# 2xVCA_SMD.net
KiCad netlist of a schematic drawn in EAGLE
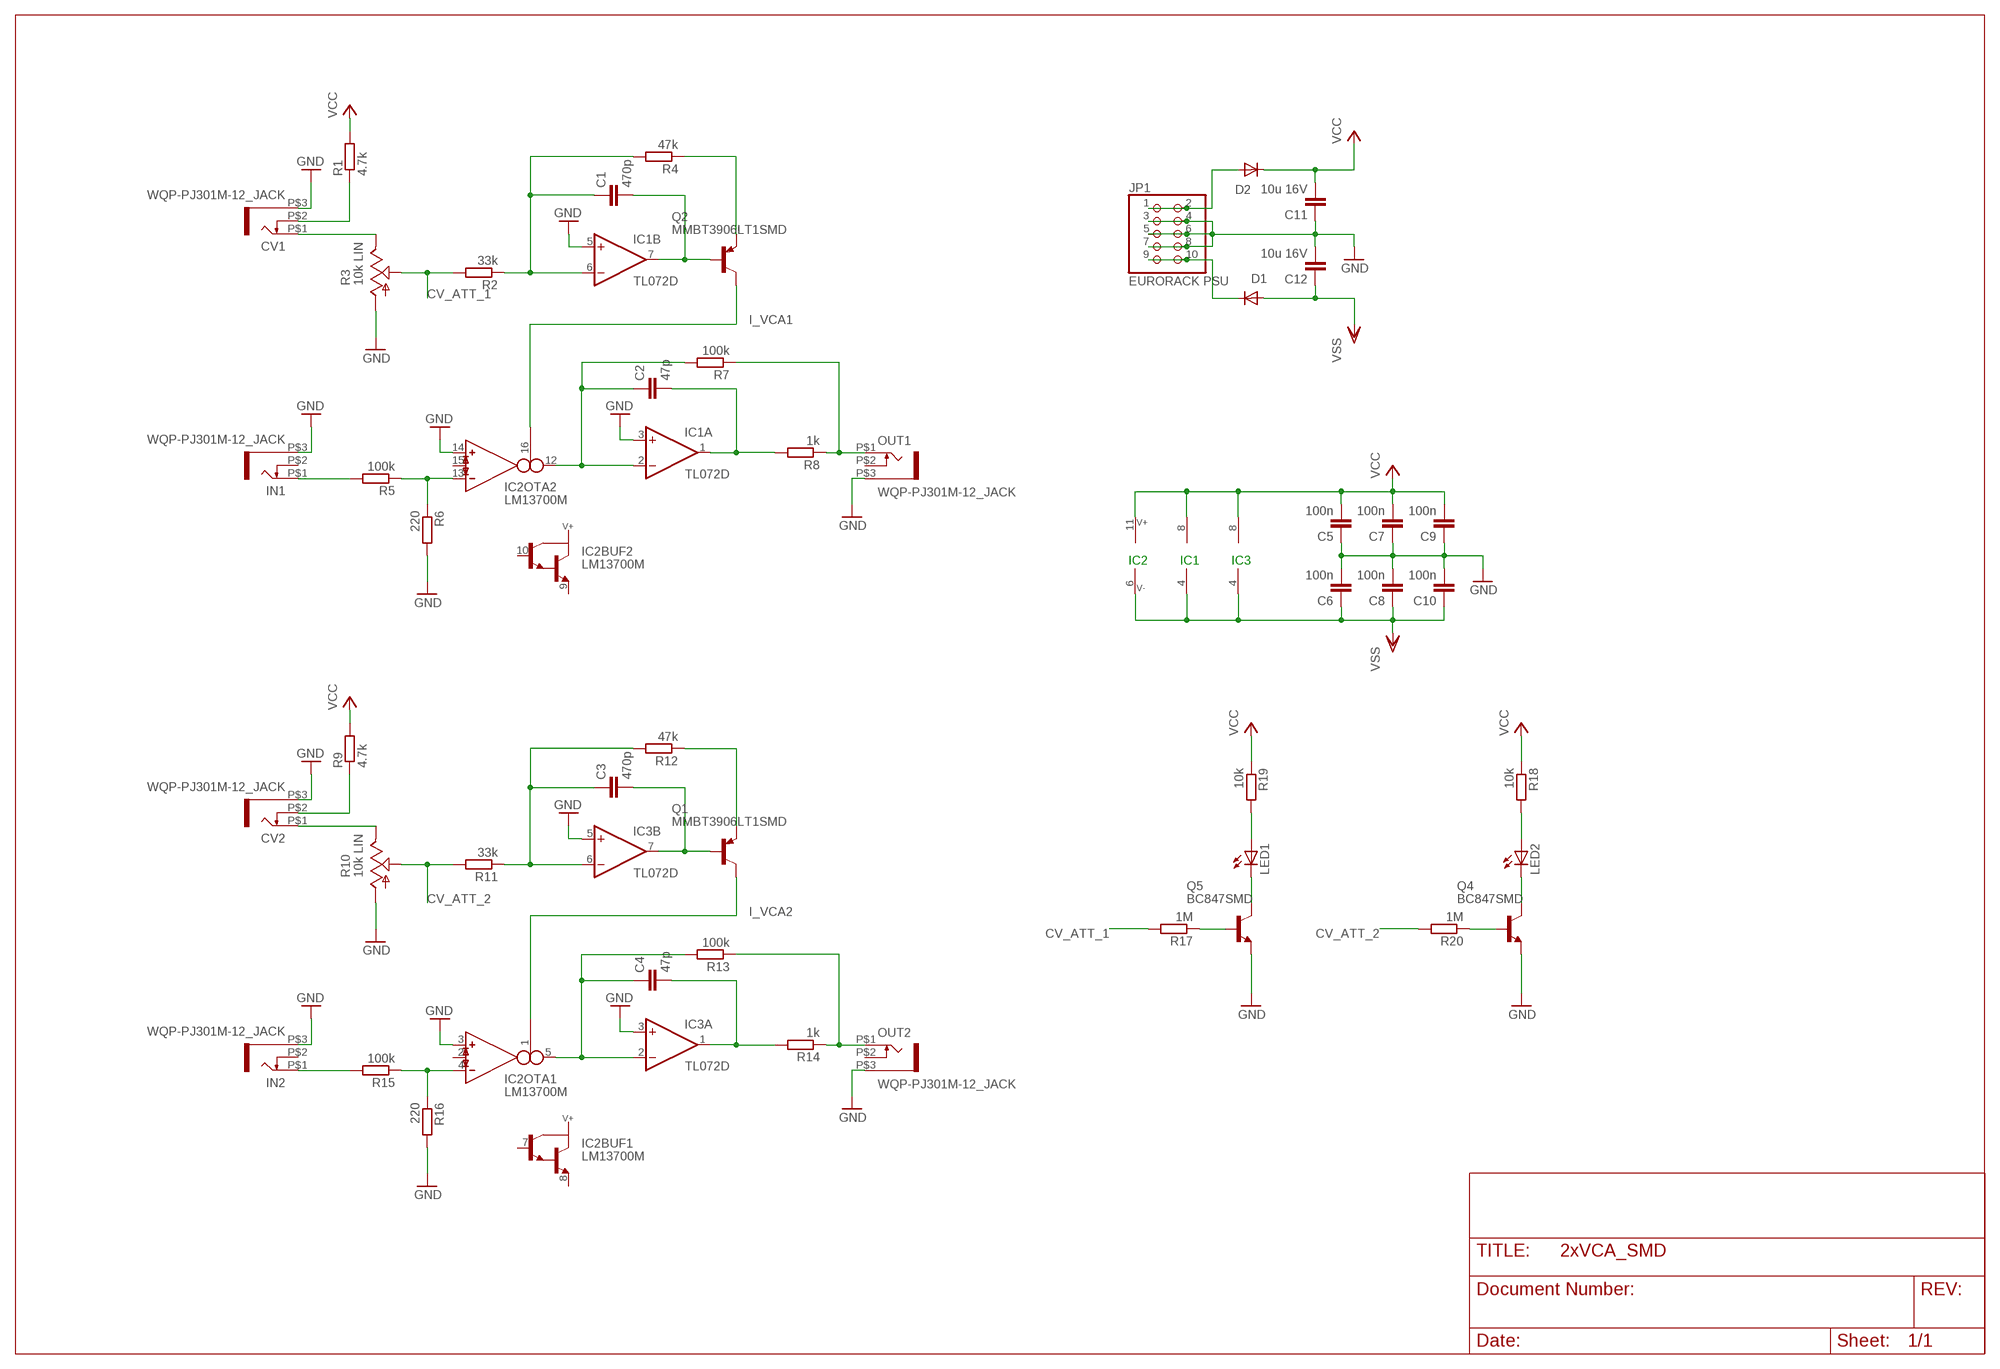
[diagram p0: schematic, sheet 1]

(export (version "E")
  (design (tool "Eeschema 10.0.6"))
  (components
    (comp (ref "C1")
      (value "470p")
      (footprint "eagle-import:C0603K")
      (libsource (lib "eagle-import") (part "C-EUC0603K"))
    )
    (comp (ref "C2")
      (value "47p")
      (footprint "eagle-import:C0603K")
      (libsource (lib "eagle-import") (part "C-EUC0603K"))
    )
    (comp (ref "C3")
      (value "470p")
      (footprint "eagle-import:C0603K")
      (libsource (lib "eagle-import") (part "C-EUC0603K"))
    )
    (comp (ref "C4")
      (value "47p")
      (footprint "eagle-import:C0603K")
      (libsource (lib "eagle-import") (part "C-EUC0603K"))
    )
    (comp (ref "C5")
      (value "100n")
      (footprint "eagle-import:C0603K")
      (libsource (lib "eagle-import") (part "C-EUC0603K"))
    )
    (comp (ref "C6")
      (value "100n")
      (footprint "eagle-import:C0603K")
      (libsource (lib "eagle-import") (part "C-EUC0603K"))
    )
    (comp (ref "C7")
      (value "100n")
      (footprint "eagle-import:C0603K")
      (libsource (lib "eagle-import") (part "C-EUC0603K"))
    )
    (comp (ref "C8")
      (value "100n")
      (footprint "eagle-import:C0603K")
      (libsource (lib "eagle-import") (part "C-EUC0603K"))
    )
    (comp (ref "C9")
      (value "100n")
      (footprint "eagle-import:C0603K")
      (libsource (lib "eagle-import") (part "C-EUC0603K"))
    )
    (comp (ref "C10")
      (value "100n")
      (footprint "eagle-import:C0603K")
      (libsource (lib "eagle-import") (part "C-EUC0603K"))
    )
    (comp (ref "C11")
      (value "10u 16V")
      (footprint "eagle-import:C1206K")
      (libsource (lib "eagle-import") (part "C-EUC1206K"))
    )
    (comp (ref "C12")
      (value "10u 16V")
      (footprint "eagle-import:C1206K")
      (libsource (lib "eagle-import") (part "C-EUC1206K"))
    )
    (comp (ref "CV1")
      (value "WQP-PJ301M-12_JACK")
      (footprint "eagle-import:WQP-PJ301M-12_JACK")
      (libsource (lib "eagle-import") (part "WQP-PJ301M-12_JACK"))
    )
    (comp (ref "CV2")
      (value "WQP-PJ301M-12_JACK")
      (footprint "eagle-import:WQP-PJ301M-12_JACK")
      (libsource (lib "eagle-import") (part "WQP-PJ301M-12_JACK"))
    )
    (comp (ref "D1")
      (value "1N5819HW")
      (footprint "eagle-import:SOD123")
      (libsource (lib "eagle-import") (part "DIODE-SOD123"))
    )
    (comp (ref "D2")
      (value "1N5819HW")
      (footprint "eagle-import:SOD123")
      (libsource (lib "eagle-import") (part "DIODE-SOD123"))
    )
    (comp (ref "IC1")
      (value "TL072D")
      (footprint "eagle-import:SO08")
      (libsource (lib "eagle-import") (part "TL072D"))
    )
    (comp (ref "IC2")
      (value "LM13700M")
      (footprint "eagle-import:SO16")
      (libsource (lib "eagle-import") (part "LM13700M"))
    )
    (comp (ref "IC3")
      (value "TL072D")
      (footprint "eagle-import:SO08")
      (libsource (lib "eagle-import") (part "TL072D"))
    )
    (comp (ref "IN1")
      (value "WQP-PJ301M-12_JACK")
      (footprint "eagle-import:WQP-PJ301M-12_JACK")
      (libsource (lib "eagle-import") (part "WQP-PJ301M-12_JACK"))
    )
    (comp (ref "IN2")
      (value "WQP-PJ301M-12_JACK")
      (footprint "eagle-import:WQP-PJ301M-12_JACK")
      (libsource (lib "eagle-import") (part "WQP-PJ301M-12_JACK"))
    )
    (comp (ref "JP1")
      (value "EURORACK PSU")
      (footprint "eagle-import:2X05")
      (libsource (lib "eagle-import") (part "PINHD-2X5"))
    )
    (comp (ref "LED1")
      (value "LED3MM")
      (footprint "eagle-import:LED3MM")
      (libsource (lib "eagle-import") (part "LED3MM"))
    )
    (comp (ref "LED2")
      (value "LED3MM")
      (footprint "eagle-import:LED3MM")
      (libsource (lib "eagle-import") (part "LED3MM"))
    )
    (comp (ref "OUT1")
      (value "WQP-PJ301M-12_JACK")
      (footprint "eagle-import:WQP-PJ301M-12_JACK")
      (libsource (lib "eagle-import") (part "WQP-PJ301M-12_JACK"))
    )
    (comp (ref "OUT2")
      (value "WQP-PJ301M-12_JACK")
      (footprint "eagle-import:WQP-PJ301M-12_JACK")
      (libsource (lib "eagle-import") (part "WQP-PJ301M-12_JACK"))
    )
    (comp (ref "Q1")
      (value "MMBT3906LT1SMD")
      (footprint "eagle-import:SOT23-BEC")
      (libsource (lib "eagle-import") (part "MMBT3906SMDLT1"))
    )
    (comp (ref "Q2")
      (value "MMBT3906LT1SMD")
      (footprint "eagle-import:SOT23-BEC")
      (libsource (lib "eagle-import") (part "MMBT3906SMDLT1"))
    )
    (comp (ref "Q4")
      (value "BC847SMD")
      (footprint "eagle-import:SOT23")
      (libsource (lib "eagle-import") (part "BC847SMD"))
    )
    (comp (ref "Q5")
      (value "BC847SMD")
      (footprint "eagle-import:SOT23")
      (libsource (lib "eagle-import") (part "BC847SMD"))
    )
    (comp (ref "R1")
      (value "4.7k")
      (footprint "eagle-import:R0603")
      (libsource (lib "eagle-import") (part "R-EU_R0603"))
    )
    (comp (ref "R2")
      (value "33k")
      (footprint "eagle-import:R0603")
      (libsource (lib "eagle-import") (part "R-EU_R0603"))
    )
    (comp (ref "R3")
      (value "10k LIN")
      (footprint "eagle-import:ALPS_POT_VERTICAL")
      (libsource (lib "eagle-import") (part "POT_USVERTICAL"))
    )
    (comp (ref "R4")
      (value "47k")
      (footprint "eagle-import:R0603")
      (libsource (lib "eagle-import") (part "R-EU_R0603"))
    )
    (comp (ref "R5")
      (value "100k")
      (footprint "eagle-import:R0603")
      (libsource (lib "eagle-import") (part "R-EU_R0603"))
    )
    (comp (ref "R6")
      (value "220")
      (footprint "eagle-import:R0603")
      (libsource (lib "eagle-import") (part "R-EU_R0603"))
    )
    (comp (ref "R7")
      (value "100k")
      (footprint "eagle-import:R0603")
      (libsource (lib "eagle-import") (part "R-EU_R0603"))
    )
    (comp (ref "R8")
      (value "1k")
      (footprint "eagle-import:R0603")
      (libsource (lib "eagle-import") (part "R-EU_R0603"))
    )
    (comp (ref "R9")
      (value "4.7k")
      (footprint "eagle-import:R0603")
      (libsource (lib "eagle-import") (part "R-EU_R0603"))
    )
    (comp (ref "R10")
      (value "10k LIN")
      (footprint "eagle-import:ALPS_POT_VERTICAL")
      (libsource (lib "eagle-import") (part "POT_USVERTICAL"))
    )
    (comp (ref "R11")
      (value "33k")
      (footprint "eagle-import:R0603")
      (libsource (lib "eagle-import") (part "R-EU_R0603"))
    )
    (comp (ref "R12")
      (value "47k")
      (footprint "eagle-import:R0603")
      (libsource (lib "eagle-import") (part "R-EU_R0603"))
    )
    (comp (ref "R13")
      (value "100k")
      (footprint "eagle-import:R0603")
      (libsource (lib "eagle-import") (part "R-EU_R0603"))
    )
    (comp (ref "R14")
      (value "1k")
      (footprint "eagle-import:R0603")
      (libsource (lib "eagle-import") (part "R-EU_R0603"))
    )
    (comp (ref "R15")
      (value "100k")
      (footprint "eagle-import:R0603")
      (libsource (lib "eagle-import") (part "R-EU_R0603"))
    )
    (comp (ref "R16")
      (value "220")
      (footprint "eagle-import:R0603")
      (libsource (lib "eagle-import") (part "R-EU_R0603"))
    )
    (comp (ref "R17")
      (value "1M")
      (footprint "eagle-import:R0603")
      (libsource (lib "eagle-import") (part "R-EU_R0603"))
    )
    (comp (ref "R18")
      (value "10k")
      (footprint "eagle-import:R0603")
      (libsource (lib "eagle-import") (part "R-EU_R0603"))
    )
    (comp (ref "R19")
      (value "10k")
      (footprint "eagle-import:R0603")
      (libsource (lib "eagle-import") (part "R-EU_R0603"))
    )
    (comp (ref "R20")
      (value "1M")
      (footprint "eagle-import:R0603")
      (libsource (lib "eagle-import") (part "R-EU_R0603"))
    )
  )
  (nets
    (net (code "1") (name "/CV_ATT_1") (class "Default")
      (node (ref "R17") (pin "2") (pinfunction "2_2") (pintype "passive"))
      (node (ref "R2") (pin "2") (pinfunction "2_2") (pintype "passive"))
      (node (ref "R3") (pin "P$2") (pinfunction "S_P$2") (pintype "passive"))
    )
    (net (code "2") (name "/CV_ATT_2") (class "Default")
      (node (ref "R10") (pin "P$2") (pinfunction "S_P$2") (pintype "passive"))
      (node (ref "R11") (pin "2") (pinfunction "2_2") (pintype "passive"))
      (node (ref "R20") (pin "2") (pinfunction "2_2") (pintype "passive"))
    )
    (net (code "3") (name "/I_VCA1") (class "Default")
      (node (ref "IC2") (pin "16") (pinfunction "I_BIAS_16") (pintype "input"))
      (node (ref "Q2") (pin "C") (pinfunction "C_C") (pintype "passive"))
    )
    (net (code "4") (name "/I_VCA2") (class "Default")
      (node (ref "IC2") (pin "1") (pinfunction "I_BIAS_1") (pintype "input"))
      (node (ref "Q1") (pin "C") (pinfunction "C_C") (pintype "passive"))
    )
    (net (code "5") (name "GND") (class "Default")
      (node (ref "C10") (pin "2") (pinfunction "2_2") (pintype "passive"))
      (node (ref "C11") (pin "1") (pinfunction "1_1") (pintype "passive"))
      (node (ref "C12") (pin "2") (pinfunction "2_2") (pintype "passive"))
      (node (ref "C5") (pin "1") (pinfunction "1_1") (pintype "passive"))
      (node (ref "C6") (pin "2") (pinfunction "2_2") (pintype "passive"))
      (node (ref "C7") (pin "1") (pinfunction "1_1") (pintype "passive"))
      (node (ref "C8") (pin "2") (pinfunction "2_2") (pintype "passive"))
      (node (ref "C9") (pin "1") (pinfunction "1_1") (pintype "passive"))
      (node (ref "CV1") (pin "P$3") (pinfunction "1_P$3") (pintype "passive"))
      (node (ref "CV2") (pin "P$3") (pinfunction "1_P$3") (pintype "passive"))
      (node (ref "IC1") (pin "3") (pinfunction "+IN_3") (pintype "input"))
      (node (ref "IC1") (pin "5") (pinfunction "+IN_5") (pintype "input"))
      (node (ref "IC2") (pin "14") (pinfunction "IN_P_14") (pintype "input"))
      (node (ref "IC2") (pin "3") (pinfunction "IN_P_3") (pintype "input"))
      (node (ref "IC3") (pin "3") (pinfunction "+IN_3") (pintype "input"))
      (node (ref "IC3") (pin "5") (pinfunction "+IN_5") (pintype "input"))
      (node (ref "IN1") (pin "P$3") (pinfunction "1_P$3") (pintype "passive"))
      (node (ref "IN2") (pin "P$3") (pinfunction "1_P$3") (pintype "passive"))
      (node (ref "JP1") (pin "3") (pinfunction "3_3") (pintype "passive"))
      (node (ref "JP1") (pin "4") (pinfunction "4_4") (pintype "passive"))
      (node (ref "JP1") (pin "5") (pinfunction "5_5") (pintype "passive"))
      (node (ref "JP1") (pin "6") (pinfunction "6_6") (pintype "passive"))
      (node (ref "JP1") (pin "7") (pinfunction "7_7") (pintype "passive"))
      (node (ref "JP1") (pin "8") (pinfunction "8_8") (pintype "passive"))
      (node (ref "OUT1") (pin "P$3") (pinfunction "1_P$3") (pintype "passive"))
      (node (ref "OUT2") (pin "P$3") (pinfunction "1_P$3") (pintype "passive"))
      (node (ref "Q4") (pin "2") (pinfunction "E_2") (pintype "passive"))
      (node (ref "Q5") (pin "2") (pinfunction "E_2") (pintype "passive"))
      (node (ref "R10") (pin "P$3") (pinfunction "A_P$3") (pintype "passive"))
      (node (ref "R16") (pin "2") (pinfunction "2_2") (pintype "passive"))
      (node (ref "R3") (pin "P$3") (pinfunction "A_P$3") (pintype "passive"))
      (node (ref "R6") (pin "2") (pinfunction "2_2") (pintype "passive"))
    )
    (net (code "6") (name "Net-(CV1-2)") (class "Default")
      (node (ref "CV1") (pin "P$1") (pinfunction "2_P$1") (pintype "passive"))
      (node (ref "R3") (pin "P$1") (pinfunction "E_P$1") (pintype "passive"))
    )
    (net (code "7") (name "Net-(CV1-3)") (class "Default")
      (node (ref "CV1") (pin "P$2") (pinfunction "3_P$2") (pintype "passive"))
      (node (ref "R1") (pin "1") (pinfunction "1_1") (pintype "passive"))
    )
    (net (code "8") (name "Net-(CV2-2)") (class "Default")
      (node (ref "CV2") (pin "P$1") (pinfunction "2_P$1") (pintype "passive"))
      (node (ref "R10") (pin "P$1") (pinfunction "E_P$1") (pintype "passive"))
    )
    (net (code "9") (name "Net-(CV2-3)") (class "Default")
      (node (ref "CV2") (pin "P$2") (pinfunction "3_P$2") (pintype "passive"))
      (node (ref "R9") (pin "1") (pinfunction "1_1") (pintype "passive"))
    )
    (net (code "10") (name "Net-(D1-PadC)") (class "Default")
      (node (ref "D1") (pin "C") (pinfunction "C_C") (pintype "passive"))
      (node (ref "JP1") (pin "10") (pinfunction "10_10") (pintype "passive"))
      (node (ref "JP1") (pin "9") (pinfunction "9_9") (pintype "passive"))
    )
    (net (code "11") (name "Net-(D2-PadA)") (class "Default")
      (node (ref "D2") (pin "A") (pinfunction "A_A") (pintype "passive"))
      (node (ref "JP1") (pin "1") (pinfunction "1_1") (pintype "passive"))
      (node (ref "JP1") (pin "2") (pinfunction "2_2") (pintype "passive"))
    )
    (net (code "12") (name "Net-(IC1A--IN)") (class "Default")
      (node (ref "C2") (pin "1") (pinfunction "1_1") (pintype "passive"))
      (node (ref "IC1") (pin "2") (pinfunction "-IN_2") (pintype "input"))
      (node (ref "IC2") (pin "12") (pinfunction "OUT_12") (pintype "output"))
      (node (ref "R7") (pin "2") (pinfunction "2_2") (pintype "passive"))
    )
    (net (code "13") (name "Net-(IC1A-OUT)") (class "Default")
      (node (ref "C2") (pin "2") (pinfunction "2_2") (pintype "passive"))
      (node (ref "IC1") (pin "1") (pinfunction "OUT_1") (pintype "output"))
      (node (ref "R8") (pin "2") (pinfunction "2_2") (pintype "passive"))
    )
    (net (code "14") (name "Net-(IC1B--IN)") (class "Default")
      (node (ref "C1") (pin "1") (pinfunction "1_1") (pintype "passive"))
      (node (ref "IC1") (pin "6") (pinfunction "-IN_6") (pintype "input"))
      (node (ref "R2") (pin "1") (pinfunction "1_1") (pintype "passive"))
      (node (ref "R4") (pin "2") (pinfunction "2_2") (pintype "passive"))
    )
    (net (code "15") (name "Net-(IC1B-OUT)") (class "Default")
      (node (ref "C1") (pin "2") (pinfunction "2_2") (pintype "passive"))
      (node (ref "IC1") (pin "7") (pinfunction "OUT_7") (pintype "output"))
      (node (ref "Q2") (pin "B") (pinfunction "B_B") (pintype "passive"))
    )
    (net (code "16") (name "Net-(IC2C-IN_N)") (class "Default")
      (node (ref "IC2") (pin "4") (pinfunction "IN_N_4") (pintype "input"))
      (node (ref "R15") (pin "1") (pinfunction "1_1") (pintype "passive"))
      (node (ref "R16") (pin "1") (pinfunction "1_1") (pintype "passive"))
    )
    (net (code "17") (name "Net-(IC2C-OUT)") (class "Default")
      (node (ref "C4") (pin "1") (pinfunction "1_1") (pintype "passive"))
      (node (ref "IC2") (pin "5") (pinfunction "OUT_5") (pintype "output"))
      (node (ref "IC3") (pin "2") (pinfunction "-IN_2") (pintype "input"))
      (node (ref "R13") (pin "2") (pinfunction "2_2") (pintype "passive"))
    )
    (net (code "18") (name "Net-(IC2D-IN_N)") (class "Default")
      (node (ref "IC2") (pin "13") (pinfunction "IN_N_13") (pintype "input"))
      (node (ref "R5") (pin "1") (pinfunction "1_1") (pintype "passive"))
      (node (ref "R6") (pin "1") (pinfunction "1_1") (pintype "passive"))
    )
    (net (code "19") (name "Net-(IC3A-OUT)") (class "Default")
      (node (ref "C4") (pin "2") (pinfunction "2_2") (pintype "passive"))
      (node (ref "IC3") (pin "1") (pinfunction "OUT_1") (pintype "output"))
      (node (ref "R14") (pin "2") (pinfunction "2_2") (pintype "passive"))
    )
    (net (code "20") (name "Net-(IC3B--IN)") (class "Default")
      (node (ref "C3") (pin "1") (pinfunction "1_1") (pintype "passive"))
      (node (ref "IC3") (pin "6") (pinfunction "-IN_6") (pintype "input"))
      (node (ref "R11") (pin "1") (pinfunction "1_1") (pintype "passive"))
      (node (ref "R12") (pin "2") (pinfunction "2_2") (pintype "passive"))
    )
    (net (code "21") (name "Net-(IC3B-OUT)") (class "Default")
      (node (ref "C3") (pin "2") (pinfunction "2_2") (pintype "passive"))
      (node (ref "IC3") (pin "7") (pinfunction "OUT_7") (pintype "output"))
      (node (ref "Q1") (pin "B") (pinfunction "B_B") (pintype "passive"))
    )
    (net (code "22") (name "Net-(IN1-2)") (class "Default")
      (node (ref "IN1") (pin "P$1") (pinfunction "2_P$1") (pintype "passive"))
      (node (ref "R5") (pin "2") (pinfunction "2_2") (pintype "passive"))
    )
    (net (code "23") (name "Net-(IN2-2)") (class "Default")
      (node (ref "IN2") (pin "P$1") (pinfunction "2_P$1") (pintype "passive"))
      (node (ref "R15") (pin "2") (pinfunction "2_2") (pintype "passive"))
    )
    (net (code "24") (name "Net-(LED1-C)") (class "Default")
      (node (ref "LED1") (pin "K") (pinfunction "C_K") (pintype "passive"))
      (node (ref "Q5") (pin "3") (pinfunction "C_3") (pintype "passive"))
    )
    (net (code "25") (name "Net-(LED1-PadA)") (class "Default")
      (node (ref "LED1") (pin "A") (pinfunction "A_A") (pintype "passive"))
      (node (ref "R19") (pin "2") (pinfunction "2_2") (pintype "passive"))
    )
    (net (code "26") (name "Net-(LED2-C)") (class "Default")
      (node (ref "LED2") (pin "K") (pinfunction "C_K") (pintype "passive"))
      (node (ref "Q4") (pin "3") (pinfunction "C_3") (pintype "passive"))
    )
    (net (code "27") (name "Net-(LED2-PadA)") (class "Default")
      (node (ref "LED2") (pin "A") (pinfunction "A_A") (pintype "passive"))
      (node (ref "R18") (pin "2") (pinfunction "2_2") (pintype "passive"))
    )
    (net (code "28") (name "Net-(OUT1-2)") (class "Default")
      (node (ref "OUT1") (pin "P$1") (pinfunction "2_P$1") (pintype "passive"))
      (node (ref "R7") (pin "1") (pinfunction "1_1") (pintype "passive"))
      (node (ref "R8") (pin "1") (pinfunction "1_1") (pintype "passive"))
    )
    (net (code "29") (name "Net-(OUT2-2)") (class "Default")
      (node (ref "OUT2") (pin "P$1") (pinfunction "2_P$1") (pintype "passive"))
      (node (ref "R13") (pin "1") (pinfunction "1_1") (pintype "passive"))
      (node (ref "R14") (pin "1") (pinfunction "1_1") (pintype "passive"))
    )
    (net (code "30") (name "Net-(Q1-PadE)") (class "Default")
      (node (ref "Q1") (pin "E") (pinfunction "E_E") (pintype "passive"))
      (node (ref "R12") (pin "1") (pinfunction "1_1") (pintype "passive"))
    )
    (net (code "31") (name "Net-(Q2-PadE)") (class "Default")
      (node (ref "Q2") (pin "E") (pinfunction "E_E") (pintype "passive"))
      (node (ref "R4") (pin "1") (pinfunction "1_1") (pintype "passive"))
    )
    (net (code "32") (name "Net-(Q4-B)") (class "Default")
      (node (ref "Q4") (pin "1") (pinfunction "B_1") (pintype "passive"))
      (node (ref "R20") (pin "1") (pinfunction "1_1") (pintype "passive"))
    )
    (net (code "33") (name "Net-(Q5-B)") (class "Default")
      (node (ref "Q5") (pin "1") (pinfunction "B_1") (pintype "passive"))
      (node (ref "R17") (pin "1") (pinfunction "1_1") (pintype "passive"))
    )
    (net (code "34") (name "VCC") (class "Default")
      (node (ref "C11") (pin "2") (pinfunction "2_2") (pintype "passive"))
      (node (ref "C5") (pin "2") (pinfunction "2_2") (pintype "passive"))
      (node (ref "C7") (pin "2") (pinfunction "2_2") (pintype "passive"))
      (node (ref "C9") (pin "2") (pinfunction "2_2") (pintype "passive"))
      (node (ref "D2") (pin "C") (pinfunction "C_C") (pintype "passive"))
      (node (ref "IC1") (pin "8") (pinfunction "V+_8") (pintype "power_in"))
      (node (ref "IC2") (pin "11") (pinfunction "V+_11") (pintype "power_in"))
      (node (ref "IC3") (pin "8") (pinfunction "V+_8") (pintype "power_in"))
      (node (ref "R1") (pin "2") (pinfunction "2_2") (pintype "passive"))
      (node (ref "R18") (pin "1") (pinfunction "1_1") (pintype "passive"))
      (node (ref "R19") (pin "1") (pinfunction "1_1") (pintype "passive"))
      (node (ref "R9") (pin "2") (pinfunction "2_2") (pintype "passive"))
    )
    (net (code "35") (name "VSS") (class "Default")
      (node (ref "C10") (pin "1") (pinfunction "1_1") (pintype "passive"))
      (node (ref "C12") (pin "1") (pinfunction "1_1") (pintype "passive"))
      (node (ref "C6") (pin "1") (pinfunction "1_1") (pintype "passive"))
      (node (ref "C8") (pin "1") (pinfunction "1_1") (pintype "passive"))
      (node (ref "D1") (pin "A") (pinfunction "A_A") (pintype "passive"))
      (node (ref "IC1") (pin "4") (pinfunction "V-_4") (pintype "power_in"))
      (node (ref "IC2") (pin "6") (pinfunction "V-_6") (pintype "power_in"))
      (node (ref "IC3") (pin "4") (pinfunction "V-_4") (pintype "power_in"))
    )
    (net (code "36") (name "unconnected-(IC2A-B-Pad7)") (class "Default")
      (node (ref "IC2") (pin "7") (pinfunction "B_7") (pintype "passive"))
    )
    (net (code "37") (name "unconnected-(IC2A-E-Pad8)") (class "Default")
      (node (ref "IC2") (pin "8") (pinfunction "E_8") (pintype "passive"))
    )
    (net (code "38") (name "unconnected-(IC2B-B-Pad10)") (class "Default")
      (node (ref "IC2") (pin "10") (pinfunction "B_10") (pintype "passive"))
    )
    (net (code "39") (name "unconnected-(IC2B-E-Pad9)") (class "Default")
      (node (ref "IC2") (pin "9") (pinfunction "E_9") (pintype "passive"))
    )
    (net (code "40") (name "unconnected-(IC2C-I_DIODE-Pad2)") (class "Default")
      (node (ref "IC2") (pin "2") (pinfunction "I_DIODE_2") (pintype "input"))
    )
    (net (code "41") (name "unconnected-(IC2D-I_DIODE-Pad15)") (class "Default")
      (node (ref "IC2") (pin "15") (pinfunction "I_DIODE_15") (pintype "input"))
    )
    (net (code "42") (name "unconnected-(IN1-3-PadP$2)") (class "Default")
      (node (ref "IN1") (pin "P$2") (pinfunction "3_P$2") (pintype "passive"))
    )
    (net (code "43") (name "unconnected-(IN2-3-PadP$2)") (class "Default")
      (node (ref "IN2") (pin "P$2") (pinfunction "3_P$2") (pintype "passive"))
    )
    (net (code "44") (name "unconnected-(OUT1-3-PadP$2)") (class "Default")
      (node (ref "OUT1") (pin "P$2") (pinfunction "3_P$2") (pintype "passive"))
    )
    (net (code "45") (name "unconnected-(OUT2-3-PadP$2)") (class "Default")
      (node (ref "OUT2") (pin "P$2") (pinfunction "3_P$2") (pintype "passive"))
    )
  )
)
